# Schematic.net
KiCad netlist of a schematic drawn in EAGLE
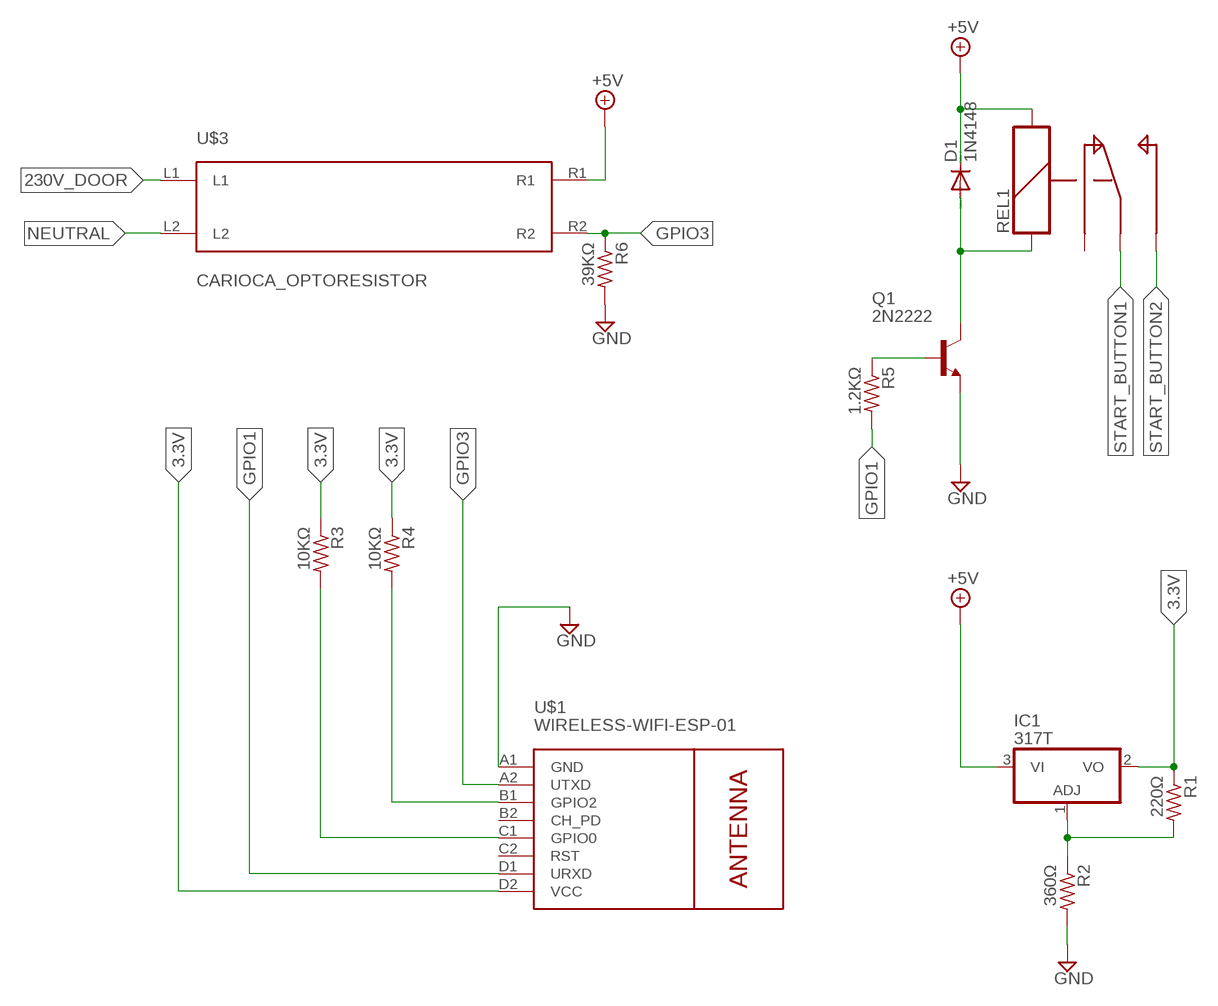
[diagram p0: schematic, sheet 1]

(export (version "E")
  (design (tool "Eeschema 10.0.6"))
  (components
    (comp (ref "D1")
      (value "1N4148")
      (footprint "eagle-import:DO35-10")
      (libsource (lib "eagle-import") (part "1N4148DO35-10"))
    )
    (comp (ref "IC1")
      (value "317T")
      (footprint "eagle-import:TO220H")
      (libsource (lib "eagle-import") (part "317T"))
    )
    (comp (ref "Q1")
      (value "2N2222")
      (footprint "eagle-import:TO18")
      (libsource (lib "eagle-import") (part "2N2222"))
    )
    (comp (ref "R1")
      (value "220Ω")
      (footprint "eagle-import:0204_5")
      (libsource (lib "eagle-import") (part "R-US_0204/5"))
    )
    (comp (ref "R2")
      (value "360Ω")
      (footprint "eagle-import:0204_5")
      (libsource (lib "eagle-import") (part "R-US_0204/5"))
    )
    (comp (ref "R3")
      (value "10KΩ")
      (footprint "eagle-import:0204_5")
      (libsource (lib "eagle-import") (part "R-US_0204/5"))
    )
    (comp (ref "R4")
      (value "10KΩ")
      (footprint "eagle-import:0204_5")
      (libsource (lib "eagle-import") (part "R-US_0204/5"))
    )
    (comp (ref "R5")
      (value "1.2KΩ")
      (footprint "eagle-import:0204_5")
      (libsource (lib "eagle-import") (part "R-US_0204/5"))
    )
    (comp (ref "R6")
      (value "39KΩ")
      (footprint "eagle-import:0204_5")
      (libsource (lib "eagle-import") (part "R-US_0204/5"))
    )
    (comp (ref "REL1")
      (value "REL-5PIN")
      (footprint "eagle-import:REL-5PIN")
      (libsource (lib "eagle-import") (part "REL-5PIN"))
    )
    (comp (ref "U$1")
      (value "WIRELESS-WIFI-ESP-01")
      (footprint "eagle-import:WIRELESS-WIFI-ESP-01")
      (libsource (lib "eagle-import") (part "WIRELESS-WIFI-ESP-01"))
    )
    (comp (ref "U$3")
      (value "CARIOCA_OPTORESISTOR")
      (footprint "eagle-import:CARIOCA_OPTORESISTOR")
      (libsource (lib "eagle-import") (part "CARIOCA_PHOTORESISTOR"))
    )
  )
  (nets
    (net (code "1") (name "+5V") (class "Default")
      (node (ref "D1") (pin "C") (pinfunction "C_C") (pintype "passive"))
      (node (ref "IC1") (pin "3") (pinfunction "VI_3") (pintype "input"))
      (node (ref "REL1") (pin "S2") (pinfunction "S2_S2") (pintype "passive"))
      (node (ref "U$3") (pin "R1") (pinfunction "R1_R1") (pintype "bidirectional"))
    )
    (net (code "2") (name "3.3V") (class "Default")
      (node (ref "IC1") (pin "2") (pinfunction "VO_2") (pintype "passive"))
      (node (ref "R1") (pin "1") (pinfunction "1_1") (pintype "passive"))
      (node (ref "R3") (pin "1") (pinfunction "1_1") (pintype "passive"))
      (node (ref "R4") (pin "1") (pinfunction "1_1") (pintype "passive"))
      (node (ref "U$1") (pin "D2") (pinfunction "VCC_D2") (pintype "power_in"))
    )
    (net (code "3") (name "230V_DOOR") (class "Default")
      (node (ref "U$3") (pin "L1") (pinfunction "L1_L1") (pintype "bidirectional"))
    )
    (net (code "4") (name "GND") (class "Default")
      (node (ref "Q1") (pin "1") (pinfunction "E_1") (pintype "passive"))
      (node (ref "R2") (pin "2") (pinfunction "2_2") (pintype "passive"))
      (node (ref "R6") (pin "2") (pinfunction "2_2") (pintype "passive"))
      (node (ref "U$1") (pin "A1") (pinfunction "GND_A1") (pintype "power_in"))
    )
    (net (code "5") (name "GPIO1") (class "Default")
      (node (ref "R5") (pin "2") (pinfunction "2_2") (pintype "passive"))
      (node (ref "U$1") (pin "D1") (pinfunction "URXD_D1") (pintype "bidirectional"))
    )
    (net (code "6") (name "GPIO3") (class "Default")
      (node (ref "R6") (pin "1") (pinfunction "1_1") (pintype "passive"))
      (node (ref "U$1") (pin "A2") (pinfunction "UTXD_A2") (pintype "bidirectional"))
      (node (ref "U$3") (pin "R2") (pinfunction "R2_R2") (pintype "bidirectional"))
    )
    (net (code "7") (name "NEUTRAL") (class "Default")
      (node (ref "U$3") (pin "L2") (pinfunction "L2_L2") (pintype "bidirectional"))
    )
    (net (code "8") (name "Net-(IC1-ADJ)") (class "Default")
      (node (ref "IC1") (pin "1") (pinfunction "ADJ_1") (pintype "input"))
      (node (ref "R1") (pin "2") (pinfunction "2_2") (pintype "passive"))
      (node (ref "R2") (pin "1") (pinfunction "1_1") (pintype "passive"))
    )
    (net (code "9") (name "Net-(Q1-B)") (class "Default")
      (node (ref "Q1") (pin "2") (pinfunction "B_2") (pintype "passive"))
      (node (ref "R5") (pin "1") (pinfunction "1_1") (pintype "passive"))
    )
    (net (code "10") (name "Net-(Q1-C)") (class "Default")
      (node (ref "D1") (pin "A") (pinfunction "A_A") (pintype "passive"))
      (node (ref "Q1") (pin "3") (pinfunction "C_3") (pintype "passive"))
      (node (ref "REL1") (pin "S1") (pinfunction "S1_S1") (pintype "passive"))
    )
    (net (code "11") (name "Net-(U$1-GPIO0)") (class "Default")
      (node (ref "R3") (pin "2") (pinfunction "2_2") (pintype "passive"))
      (node (ref "U$1") (pin "C1") (pinfunction "GPIO0_C1") (pintype "bidirectional"))
    )
    (net (code "12") (name "Net-(U$1-GPIO2)") (class "Default")
      (node (ref "R4") (pin "2") (pinfunction "2_2") (pintype "passive"))
      (node (ref "U$1") (pin "B1") (pinfunction "GPIO2_B1") (pintype "bidirectional"))
    )
    (net (code "13") (name "START_BUTTON1") (class "Default")
      (node (ref "REL1") (pin "C") (pinfunction "C_C") (pintype "passive"))
    )
    (net (code "14") (name "START_BUTTON2") (class "Default")
      (node (ref "REL1") (pin "O") (pinfunction "O_O") (pintype "passive"))
    )
    (net (code "15") (name "unconnected-(REL1-PadS)") (class "Default")
      (node (ref "REL1") (pin "S") (pinfunction "S_S") (pintype "passive"))
    )
    (net (code "16") (name "unconnected-(U$1-CH_PD-PadB2)") (class "Default")
      (node (ref "U$1") (pin "B2") (pinfunction "CH_PD_B2") (pintype "bidirectional"))
    )
    (net (code "17") (name "unconnected-(U$1-RST-PadC2)") (class "Default")
      (node (ref "U$1") (pin "C2") (pinfunction "RST_C2") (pintype "bidirectional"))
    )
  )
)
